# design.net
KiCad netlist of a schematic drawn in Altium Designer
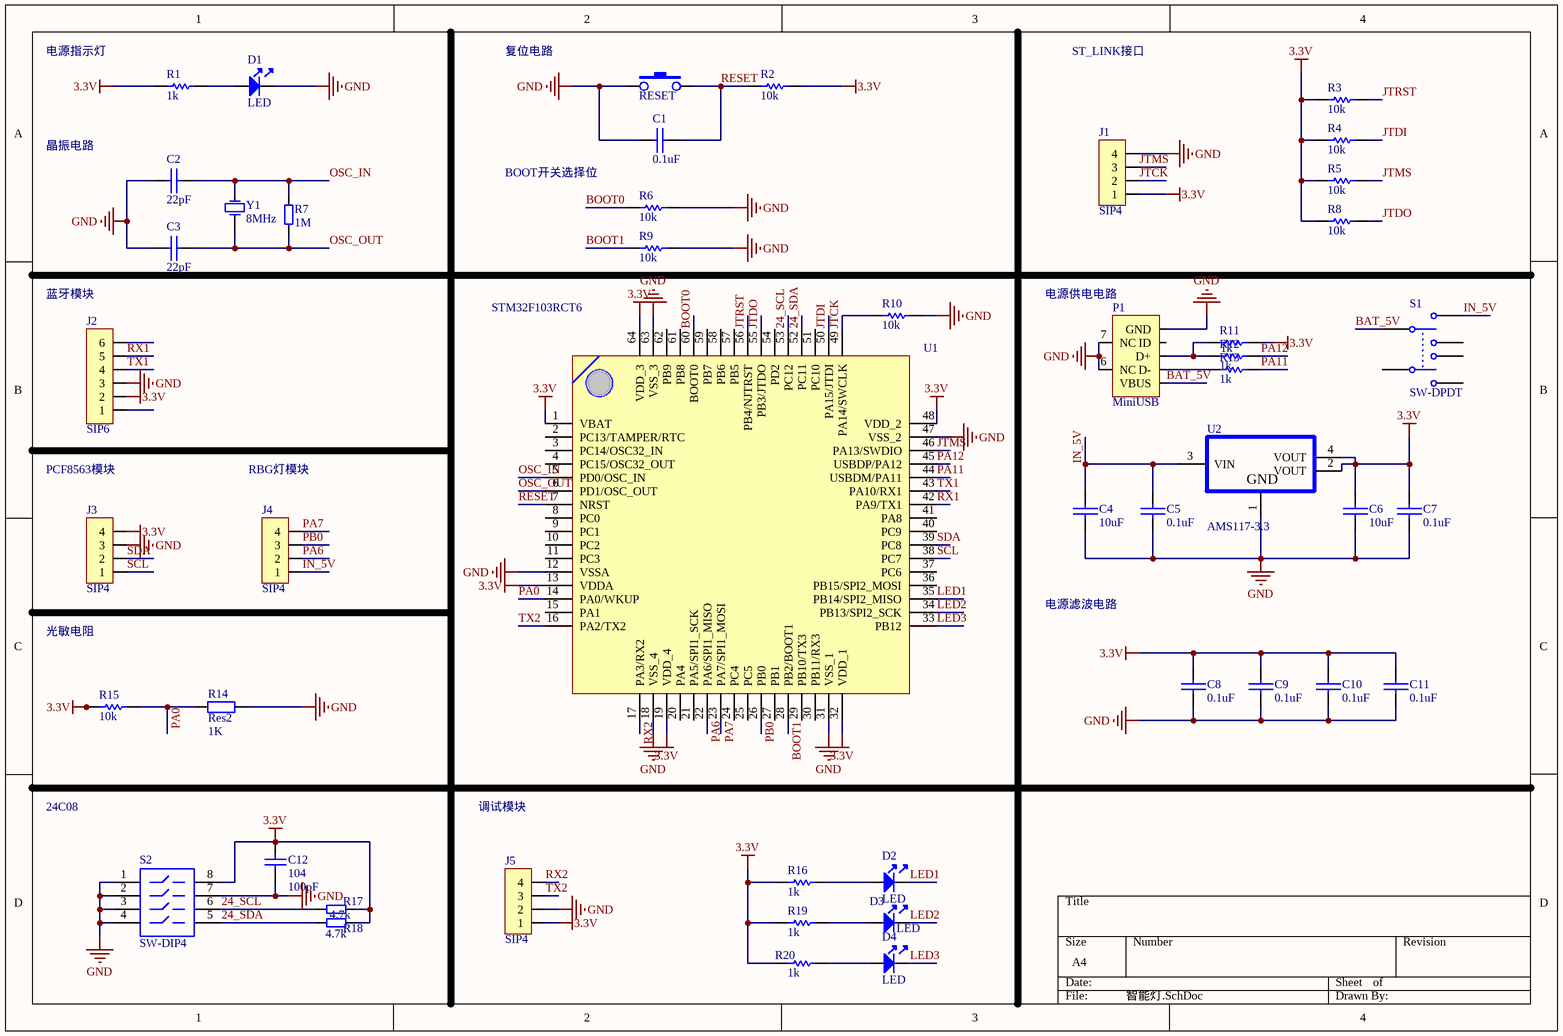
[diagram p0: 智能灯.SchDoc]

(export (version "E")
  (design (tool "Eeschema 10.0.6"))
  (components
    (comp (ref "C1")
      (value "0.1uF")
      (footprint "0805c")
      (description "Capacitor/小容量电容")
      (libsource (lib "狗尾巴草设计室") (part "CAP"))
    )
    (comp (ref "C2")
      (value "22pF")
      (footprint "0805c")
      (description "Capacitor/小容量电容")
      (libsource (lib "狗尾巴草设计室") (part "CAP"))
    )
    (comp (ref "C3")
      (value "22pF")
      (footprint "0805c")
      (description "Capacitor/小容量电容")
      (libsource (lib "狗尾巴草设计室") (part "CAP"))
    )
    (comp (ref "C4")
      (value "10uF")
      (footprint "0805c")
      (description "Capacitor/小容量电容")
      (libsource (lib "狗尾巴草设计室") (part "CAP"))
    )
    (comp (ref "C5")
      (value "0.1uF")
      (footprint "0805c")
      (description "Capacitor/小容量电容")
      (libsource (lib "狗尾巴草设计室") (part "CAP"))
    )
    (comp (ref "C6")
      (value "10uF")
      (footprint "0805c")
      (description "Capacitor/小容量电容")
      (libsource (lib "狗尾巴草设计室") (part "CAP"))
    )
    (comp (ref "C7")
      (value "0.1uF")
      (footprint "0805c")
      (description "Capacitor/小容量电容")
      (libsource (lib "狗尾巴草设计室") (part "CAP"))
    )
    (comp (ref "C8")
      (value "0.1uF")
      (footprint "0805c")
      (description "Capacitor/小容量电容")
      (libsource (lib "狗尾巴草设计室") (part "CAP"))
    )
    (comp (ref "C9")
      (value "0.1uF")
      (footprint "0805c")
      (description "Capacitor/小容量电容")
      (libsource (lib "狗尾巴草设计室") (part "CAP"))
    )
    (comp (ref "C10")
      (value "0.1uF")
      (footprint "0805c")
      (description "Capacitor/小容量电容")
      (libsource (lib "狗尾巴草设计室") (part "CAP"))
    )
    (comp (ref "C11")
      (value "0.1uF")
      (footprint "0805c")
      (description "Capacitor/小容量电容")
      (libsource (lib "狗尾巴草设计室") (part "CAP"))
    )
    (comp (ref "C12")
      (value "104")
      (footprint "0805C")
      (description "Capacitor")
      (fields (field (name "ALTIUM_VALUE") "100pF") (field (name "PUBLISHER") "Altium Limited"))
      (libsource (lib "Miscellaneous Devices") (part "Cap"))
    )
    (comp (ref "D1") (value "LED") (footprint "0805d") (libsource (lib "狗尾巴草设计室") (part "LED")))
    (comp (ref "D2") (value "LED") (footprint "0805d") (libsource (lib "狗尾巴草设计室") (part "LED")))
    (comp (ref "D3") (value "LED") (footprint "0805d") (libsource (lib "狗尾巴草设计室") (part "LED")))
    (comp (ref "D4") (value "LED") (footprint "0805d") (libsource (lib "狗尾巴草设计室") (part "LED")))
    (comp (ref "J1") (value "SIP4") (footprint "P4_2.54-1") (libsource (lib "狗尾巴草设计室") (part "SIP4")))
    (comp (ref "J2") (value "SIP6") (footprint "P6_2.54-3") (libsource (lib "狗尾巴草设计室") (part "SIP6")))
    (comp (ref "J3") (value "SIP4") (footprint "P4_2.54-3") (libsource (lib "狗尾巴草设计室") (part "SIP4")))
    (comp (ref "J4") (value "SIP4") (footprint "P4_2.54-1") (libsource (lib "狗尾巴草设计室") (part "SIP4")))
    (comp (ref "J5") (value "SIP4") (footprint "P4_2.54-1") (libsource (lib "狗尾巴草设计室") (part "SIP4")))
    (comp (ref "P1") (value "MiniUSB") (footprint "USB_MINI_5P") (libsource (lib "狗尾巴草设计室") (part "MiniUSB")))
    (comp (ref "R1") (value "1k") (footprint "0805r") (libsource (lib "狗尾巴草设计室") (part "Res")))
    (comp (ref "R2") (value "10k") (footprint "0805r") (libsource (lib "狗尾巴草设计室") (part "Res")))
    (comp (ref "R3") (value "10k") (footprint "0805r") (libsource (lib "狗尾巴草设计室") (part "Res")))
    (comp (ref "R4") (value "10k") (footprint "0805r") (libsource (lib "狗尾巴草设计室") (part "Res")))
    (comp (ref "R5") (value "10k") (footprint "0805r") (libsource (lib "狗尾巴草设计室") (part "Res")))
    (comp (ref "R6") (value "10k") (footprint "0805r") (libsource (lib "狗尾巴草设计室") (part "Res")))
    (comp (ref "R7") (value "1M") (footprint "0805R") (libsource (lib "狗尾巴草设计室") (part "Res1")))
    (comp (ref "R8") (value "10k") (footprint "0805r") (libsource (lib "狗尾巴草设计室") (part "Res")))
    (comp (ref "R9") (value "10k") (footprint "0805r") (libsource (lib "狗尾巴草设计室") (part "Res")))
    (comp (ref "R10") (value "10k") (footprint "0805r") (libsource (lib "狗尾巴草设计室") (part "Res")))
    (comp (ref "R11") (value "1k") (footprint "0805r") (libsource (lib "狗尾巴草设计室") (part "Res")))
    (comp (ref "R12") (value "1k") (footprint "0805r") (libsource (lib "狗尾巴草设计室") (part "Res")))
    (comp (ref "R13") (value "1k") (footprint "0805r") (libsource (lib "狗尾巴草设计室") (part "Res")))
    (comp (ref "R14")
      (value "Res2")
      (footprint "AXIAL0.3")
      (description "Resistor")
      (fields (field (name "ALTIUM_VALUE") "1K") (field (name "PUBLISHER") "Altium Limited"))
      (libsource (lib "Miscellaneous Devices") (part "Res2"))
    )
    (comp (ref "R15") (value "10k") (footprint "0805R") (libsource (lib "狗尾巴草设计室") (part "Res_1")))
    (comp (ref "R16") (value "1k") (footprint "0603R") (libsource (lib "狗尾巴草设计室") (part "Res_2")))
    (comp (ref "R17") (value "4.7k") (footprint "0805R") (libsource (lib "狗尾巴草设计室") (part "Res1")))
    (comp (ref "R18") (value "4.7k") (footprint "0805R") (libsource (lib "狗尾巴草设计室") (part "Res1")))
    (comp (ref "R19") (value "1k") (footprint "0603R") (libsource (lib "狗尾巴草设计室") (part "Res_2")))
    (comp (ref "R20") (value "1k") (footprint "0603R") (libsource (lib "狗尾巴草设计室") (part "Res_2")))
    (comp (ref "RESET")
      (value "SW-PB_DIP")
      (footprint "KEY_SIM2P")
      (libsource (lib "狗尾巴草设计室") (part "SW-PB_DIP"))
    )
    (comp (ref "S1")
      (value "SW-DPDT")
      (footprint "DPDT-6")
      (description "Double-Pole, Double-Throw Switch")
      (fields (field (name "PUBLISHER") "Altium Limited"))
      (libsource (lib "Miscellaneous Devices") (part "SW-DPDT"))
    )
    (comp (ref "S2")
      (value "SW-DIP4")
      (footprint "DIP-8")
      (description "DIP Switch")
      (fields (field (name "PUBLISHER") "Altium Limited"))
      (libsource (lib "Miscellaneous Devices") (part "SW-DIP4"))
    )
    (comp (ref "U1")
      (value "STM32F103RCT6")
      (footprint "LQFP64-0.5MM")
      (description "LQFP64")
      (libsource (lib "狗尾巴草设计室") (part "STM32F103RD"))
    )
    (comp (ref "U2")
      (value "AMS117-3.3")
      (footprint "SOT-223")
      (libsource (lib "狗尾巴草设计室") (part "AMS117-3.3"))
    )
    (comp (ref "Y1") (value "8MHz") (footprint "0.1UF") (libsource (lib "狗尾巴草设计室") (part "J晶振-3")))
  )
  (nets
    (net (code "1") (name "/24_SCL") (class "Default")
      (node (ref "R17") (pin "1") (pintype "passive"))
      (node (ref "S2") (pin "6") (pinfunction "6_6") (pintype "passive"))
      (node (ref "U1") (pin "53") (pinfunction "PC12_53") (pintype "passive"))
    )
    (net (code "2") (name "/24_SDA") (class "Default")
      (node (ref "R18") (pin "1") (pintype "passive"))
      (node (ref "S2") (pin "5") (pinfunction "5_5") (pintype "passive"))
      (node (ref "U1") (pin "52") (pinfunction "PC11_52") (pintype "passive"))
    )
    (net (code "3") (name "/BAT_5V") (class "Default")
      (node (ref "P1") (pin "1") (pinfunction "VBUS_1") (pintype "passive"))
      (node (ref "S1") (pin "1") (pinfunction "1_1") (pintype "passive"))
    )
    (net (code "4") (name "/BOOT0") (class "Default")
      (node (ref "R6") (pin "1") (pinfunction "1_1") (pintype "passive"))
      (node (ref "U1") (pin "60") (pinfunction "BOOT0_60") (pintype "passive"))
    )
    (net (code "5") (name "/BOOT1") (class "Default")
      (node (ref "R9") (pin "1") (pinfunction "1_1") (pintype "passive"))
      (node (ref "U1") (pin "28") (pinfunction "PB2/BOOT1_28") (pintype "passive"))
    )
    (net (code "6") (name "/IN_5V") (class "Default")
      (node (ref "C4") (pin "1") (pinfunction "1_1") (pintype "passive"))
      (node (ref "C5") (pin "1") (pinfunction "1_1") (pintype "passive"))
      (node (ref "J4") (pin "1") (pinfunction "1_1") (pintype "passive"))
      (node (ref "S1") (pin "2") (pinfunction "2_2") (pintype "passive"))
      (node (ref "U2") (pin "3") (pinfunction "VIN_3") (pintype "passive"))
    )
    (net (code "7") (name "/JTCK") (class "Default")
      (node (ref "J1") (pin "2") (pinfunction "2_2") (pintype "passive"))
      (node (ref "R10") (pin "1") (pinfunction "1_1") (pintype "passive"))
      (node (ref "U1") (pin "49") (pinfunction "PA14/SWCLK_49") (pintype "passive"))
    )
    (net (code "8") (name "/JTDI") (class "Default")
      (node (ref "R4") (pin "2") (pinfunction "2_2") (pintype "passive"))
      (node (ref "U1") (pin "50") (pinfunction "PA15/JTDI_50") (pintype "passive"))
    )
    (net (code "9") (name "/JTDO") (class "Default")
      (node (ref "R8") (pin "2") (pinfunction "2_2") (pintype "passive"))
      (node (ref "U1") (pin "55") (pinfunction "PB3/JTDO_55") (pintype "passive"))
    )
    (net (code "10") (name "/JTMS") (class "Default")
      (node (ref "J1") (pin "3") (pinfunction "3_3") (pintype "passive"))
      (node (ref "R5") (pin "2") (pinfunction "2_2") (pintype "passive"))
      (node (ref "U1") (pin "46") (pinfunction "PA13/SWDIO_46") (pintype "passive"))
    )
    (net (code "11") (name "/JTRST") (class "Default")
      (node (ref "R3") (pin "2") (pinfunction "2_2") (pintype "passive"))
      (node (ref "U1") (pin "56") (pinfunction "PB4/NJTRST_56") (pintype "passive"))
    )
    (net (code "12") (name "/LED1") (class "Default")
      (node (ref "D2") (pin "2") (pinfunction "2_2") (pintype "passive"))
      (node (ref "U1") (pin "35") (pinfunction "PB14/SPI2_MISO_35") (pintype "passive"))
    )
    (net (code "13") (name "/LED2") (class "Default")
      (node (ref "D3") (pin "2") (pinfunction "2_2") (pintype "passive"))
      (node (ref "U1") (pin "34") (pinfunction "PB13/SPI2_SCK_34") (pintype "passive"))
    )
    (net (code "14") (name "/LED3") (class "Default")
      (node (ref "D4") (pin "2") (pinfunction "2_2") (pintype "passive"))
      (node (ref "U1") (pin "33") (pinfunction "PB12_33") (pintype "passive"))
    )
    (net (code "15") (name "/OSC_IN") (class "Default")
      (node (ref "C2") (pin "2") (pinfunction "2_2") (pintype "passive"))
      (node (ref "R7") (pin "1") (pintype "passive"))
      (node (ref "U1") (pin "5") (pinfunction "PD0/OSC_IN_5") (pintype "passive"))
      (node (ref "Y1") (pin "2") (pinfunction "OSC2_2") (pintype "passive"))
    )
    (net (code "16") (name "/OSC_OUT") (class "Default")
      (node (ref "C3") (pin "2") (pinfunction "2_2") (pintype "passive"))
      (node (ref "R7") (pin "2") (pintype "passive"))
      (node (ref "U1") (pin "6") (pinfunction "PD1/OSC_OUT_6") (pintype "passive"))
      (node (ref "Y1") (pin "1") (pinfunction "OSC1_1") (pintype "passive"))
    )
    (net (code "17") (name "/PA0") (class "Default")
      (node (ref "R14") (pin "1") (pinfunction "1_1") (pintype "passive"))
      (node (ref "R15") (pin "2") (pinfunction "2_2") (pintype "passive"))
      (node (ref "U1") (pin "14") (pinfunction "PA0/WKUP_14") (pintype "passive"))
    )
    (net (code "18") (name "/PA6") (class "Default")
      (node (ref "J4") (pin "2") (pinfunction "2_2") (pintype "passive"))
      (node (ref "U1") (pin "22") (pinfunction "PA6/SPI1_MISO_22") (pintype "passive"))
    )
    (net (code "19") (name "/PA7") (class "Default")
      (node (ref "J4") (pin "4") (pinfunction "4_4") (pintype "passive"))
      (node (ref "U1") (pin "23") (pinfunction "PA7/SPI1_MOSI_23") (pintype "passive"))
    )
    (net (code "20") (name "/PA11") (class "Default")
      (node (ref "R13") (pin "2") (pinfunction "2_2") (pintype "passive"))
      (node (ref "U1") (pin "44") (pinfunction "USBDM/PA11_44") (pintype "passive"))
    )
    (net (code "21") (name "/PA12") (class "Default")
      (node (ref "R12") (pin "2") (pinfunction "2_2") (pintype "passive"))
      (node (ref "U1") (pin "45") (pinfunction "USBDP/PA12_45") (pintype "passive"))
    )
    (net (code "22") (name "/PB0") (class "Default")
      (node (ref "J4") (pin "3") (pinfunction "3_3") (pintype "passive"))
      (node (ref "U1") (pin "26") (pinfunction "PB0_26") (pintype "passive"))
    )
    (net (code "23") (name "/RESET") (class "Default")
      (node (ref "C1") (pin "1") (pinfunction "1_1") (pintype "passive"))
      (node (ref "R2") (pin "1") (pinfunction "1_1") (pintype "passive"))
      (node (ref "RESET") (pin "2") (pintype "passive"))
      (node (ref "U1") (pin "7") (pinfunction "NRST_7") (pintype "passive"))
    )
    (net (code "24") (name "/RX1") (class "Default")
      (node (ref "J2") (pin "5") (pinfunction "5_5") (pintype "passive"))
      (node (ref "U1") (pin "42") (pinfunction "PA9/TX1_42") (pintype "passive"))
    )
    (net (code "25") (name "/RX2") (class "Default")
      (node (ref "J5") (pin "4") (pinfunction "4_4") (pintype "passive"))
      (node (ref "U1") (pin "17") (pinfunction "PA3/RX2_17") (pintype "passive"))
    )
    (net (code "26") (name "/SCL") (class "Default")
      (node (ref "J3") (pin "1") (pinfunction "1_1") (pintype "passive"))
      (node (ref "U1") (pin "38") (pinfunction "PC7_38") (pintype "passive"))
    )
    (net (code "27") (name "/SDA") (class "Default")
      (node (ref "J3") (pin "2") (pinfunction "2_2") (pintype "passive"))
      (node (ref "U1") (pin "39") (pinfunction "PC8_39") (pintype "passive"))
    )
    (net (code "28") (name "/TX1") (class "Default")
      (node (ref "J2") (pin "4") (pinfunction "4_4") (pintype "passive"))
      (node (ref "U1") (pin "43") (pinfunction "PA10/RX1_43") (pintype "passive"))
    )
    (net (code "29") (name "/TX2") (class "Default")
      (node (ref "J5") (pin "3") (pinfunction "3_3") (pintype "passive"))
      (node (ref "U1") (pin "16") (pinfunction "PA2/TX2_16") (pintype "passive"))
    )
    (net (code "30") (name "3.3V") (class "Default")
      (node (ref "C10") (pin "1") (pinfunction "1_1") (pintype "passive"))
      (node (ref "C11") (pin "1") (pinfunction "1_1") (pintype "passive"))
      (node (ref "C12") (pin "2") (pinfunction "2_2") (pintype "passive"))
      (node (ref "C6") (pin "1") (pinfunction "1_1") (pintype "passive"))
      (node (ref "C7") (pin "1") (pinfunction "1_1") (pintype "passive"))
      (node (ref "C8") (pin "1") (pinfunction "1_1") (pintype "passive"))
      (node (ref "C9") (pin "1") (pinfunction "1_1") (pintype "passive"))
      (node (ref "J1") (pin "1") (pinfunction "1_1") (pintype "passive"))
      (node (ref "J2") (pin "2") (pinfunction "2_2") (pintype "passive"))
      (node (ref "J3") (pin "4") (pinfunction "4_4") (pintype "passive"))
      (node (ref "J5") (pin "1") (pinfunction "1_1") (pintype "passive"))
      (node (ref "R1") (pin "1") (pinfunction "1_1") (pintype "passive"))
      (node (ref "R11") (pin "2") (pinfunction "2_2") (pintype "passive"))
      (node (ref "R15") (pin "1") (pinfunction "1_1") (pintype "passive"))
      (node (ref "R16") (pin "1") (pinfunction "1_1") (pintype "passive"))
      (node (ref "R17") (pin "2") (pintype "passive"))
      (node (ref "R18") (pin "2") (pintype "passive"))
      (node (ref "R19") (pin "1") (pinfunction "1_1") (pintype "passive"))
      (node (ref "R2") (pin "2") (pinfunction "2_2") (pintype "passive"))
      (node (ref "R20") (pin "1") (pinfunction "1_1") (pintype "passive"))
      (node (ref "R3") (pin "1") (pinfunction "1_1") (pintype "passive"))
      (node (ref "R4") (pin "1") (pinfunction "1_1") (pintype "passive"))
      (node (ref "R5") (pin "1") (pinfunction "1_1") (pintype "passive"))
      (node (ref "R8") (pin "1") (pinfunction "1_1") (pintype "passive"))
      (node (ref "S2") (pin "8") (pinfunction "8_8") (pintype "passive"))
      (node (ref "U1") (pin "1") (pinfunction "VBAT_1") (pintype "passive"))
      (node (ref "U1") (pin "13") (pinfunction "VDDA_13") (pintype "passive"))
      (node (ref "U1") (pin "19") (pinfunction "VDD_4_19") (pintype "passive"))
      (node (ref "U1") (pin "32") (pinfunction "VDD_1_32") (pintype "passive"))
      (node (ref "U1") (pin "48") (pinfunction "VDD_2_48") (pintype "passive"))
      (node (ref "U1") (pin "64") (pinfunction "VDD_3_64") (pintype "passive"))
      (node (ref "U2") (pin "2") (pinfunction "VOUT_2") (pintype "passive"))
      (node (ref "U2") (pin "4") (pinfunction "VOUT_4") (pintype "passive"))
    )
    (net (code "31") (name "GND") (class "Default")
      (node (ref "C1") (pin "2") (pinfunction "2_2") (pintype "passive"))
      (node (ref "C10") (pin "2") (pinfunction "2_2") (pintype "passive"))
      (node (ref "C11") (pin "2") (pinfunction "2_2") (pintype "passive"))
      (node (ref "C12") (pin "1") (pinfunction "1_1") (pintype "passive"))
      (node (ref "C2") (pin "1") (pinfunction "1_1") (pintype "passive"))
      (node (ref "C3") (pin "1") (pinfunction "1_1") (pintype "passive"))
      (node (ref "C4") (pin "2") (pinfunction "2_2") (pintype "passive"))
      (node (ref "C5") (pin "2") (pinfunction "2_2") (pintype "passive"))
      (node (ref "C6") (pin "2") (pinfunction "2_2") (pintype "passive"))
      (node (ref "C7") (pin "2") (pinfunction "2_2") (pintype "passive"))
      (node (ref "C8") (pin "2") (pinfunction "2_2") (pintype "passive"))
      (node (ref "C9") (pin "2") (pinfunction "2_2") (pintype "passive"))
      (node (ref "D1") (pin "2") (pinfunction "2_2") (pintype "passive"))
      (node (ref "J1") (pin "4") (pinfunction "4_4") (pintype "passive"))
      (node (ref "J2") (pin "3") (pinfunction "3_3") (pintype "passive"))
      (node (ref "J3") (pin "3") (pinfunction "3_3") (pintype "passive"))
      (node (ref "J5") (pin "2") (pinfunction "2_2") (pintype "passive"))
      (node (ref "P1") (pin "5") (pinfunction "GND_5") (pintype "passive"))
      (node (ref "P1") (pin "6") (pinfunction "NC_6") (pintype "passive"))
      (node (ref "P1") (pin "7") (pinfunction "NC_7") (pintype "passive"))
      (node (ref "R10") (pin "2") (pinfunction "2_2") (pintype "passive"))
      (node (ref "R14") (pin "2") (pinfunction "2_2") (pintype "passive"))
      (node (ref "R6") (pin "2") (pinfunction "2_2") (pintype "passive"))
      (node (ref "R9") (pin "2") (pinfunction "2_2") (pintype "passive"))
      (node (ref "RESET") (pin "1") (pintype "passive"))
      (node (ref "S2") (pin "1") (pinfunction "1_1") (pintype "passive"))
      (node (ref "S2") (pin "2") (pinfunction "2_2") (pintype "passive"))
      (node (ref "S2") (pin "3") (pinfunction "3_3") (pintype "passive"))
      (node (ref "S2") (pin "4") (pinfunction "4_4") (pintype "passive"))
      (node (ref "S2") (pin "7") (pinfunction "7_7") (pintype "passive"))
      (node (ref "U1") (pin "12") (pinfunction "VSSA_12") (pintype "passive"))
      (node (ref "U1") (pin "18") (pinfunction "VSS_4_18") (pintype "passive"))
      (node (ref "U1") (pin "31") (pinfunction "VSS_1_31") (pintype "passive"))
      (node (ref "U1") (pin "47") (pinfunction "VSS_2_47") (pintype "passive"))
      (node (ref "U1") (pin "63") (pinfunction "VSS_3_63") (pintype "passive"))
      (node (ref "U2") (pin "1") (pinfunction "GND_1") (pintype "passive"))
    )
    (net (code "32") (name "Net-(D1-Pad1)") (class "Default")
      (node (ref "D1") (pin "1") (pinfunction "1_1") (pintype "passive"))
      (node (ref "R1") (pin "2") (pinfunction "2_2") (pintype "passive"))
    )
    (net (code "33") (name "Net-(D2-Pad1)") (class "Default")
      (node (ref "D2") (pin "1") (pinfunction "1_1") (pintype "passive"))
      (node (ref "R16") (pin "2") (pinfunction "2_2") (pintype "passive"))
    )
    (net (code "34") (name "Net-(D3-Pad1)") (class "Default")
      (node (ref "D3") (pin "1") (pinfunction "1_1") (pintype "passive"))
      (node (ref "R19") (pin "2") (pinfunction "2_2") (pintype "passive"))
    )
    (net (code "35") (name "Net-(D4-Pad1)") (class "Default")
      (node (ref "D4") (pin "1") (pinfunction "1_1") (pintype "passive"))
      (node (ref "R20") (pin "2") (pinfunction "2_2") (pintype "passive"))
    )
    (net (code "36") (name "Net-(P1-D+)") (class "Default")
      (node (ref "P1") (pin "3") (pinfunction "D+_3") (pintype "passive"))
      (node (ref "R11") (pin "1") (pinfunction "1_1") (pintype "passive"))
      (node (ref "R12") (pin "1") (pinfunction "1_1") (pintype "passive"))
    )
    (net (code "37") (name "Net-(P1-D-)") (class "Default")
      (node (ref "P1") (pin "2") (pinfunction "D-_2") (pintype "passive"))
      (node (ref "R13") (pin "1") (pinfunction "1_1") (pintype "passive"))
    )
    (net (code "38") (name "unconnected-(J2-Pad1)") (class "Default")
      (node (ref "J2") (pin "1") (pinfunction "1_1") (pintype "passive"))
    )
    (net (code "39") (name "unconnected-(J2-Pad6)") (class "Default")
      (node (ref "J2") (pin "6") (pinfunction "6_6") (pintype "passive"))
    )
    (net (code "40") (name "unconnected-(P1-ID-Pad4)") (class "Default")
      (node (ref "P1") (pin "4") (pinfunction "ID_4") (pintype "passive"))
    )
    (net (code "41") (name "unconnected-(S1-Pad3)") (class "Default")
      (node (ref "S1") (pin "3") (pinfunction "3_3") (pintype "passive"))
    )
    (net (code "42") (name "unconnected-(S1-Pad4)") (class "Default")
      (node (ref "S1") (pin "4") (pinfunction "4_4") (pintype "passive"))
    )
    (net (code "43") (name "unconnected-(S1-Pad5)") (class "Default")
      (node (ref "S1") (pin "5") (pinfunction "5_5") (pintype "passive"))
    )
    (net (code "44") (name "unconnected-(S1-Pad6)") (class "Default")
      (node (ref "S1") (pin "6") (pinfunction "6_6") (pintype "passive"))
    )
    (net (code "45") (name "unconnected-(U1-PA1-Pad15)") (class "Default")
      (node (ref "U1") (pin "15") (pinfunction "PA1_15") (pintype "passive"))
    )
    (net (code "46") (name "unconnected-(U1-PA4-Pad20)") (class "Default")
      (node (ref "U1") (pin "20") (pinfunction "PA4_20") (pintype "passive"))
    )
    (net (code "47") (name "unconnected-(U1-PA5{slash}SPI1_SCK-Pad21)") (class "Default")
      (node (ref "U1") (pin "21") (pinfunction "PA5/SPI1_SCK_21") (pintype "passive"))
    )
    (net (code "48") (name "unconnected-(U1-PA8-Pad41)") (class "Default")
      (node (ref "U1") (pin "41") (pinfunction "PA8_41") (pintype "passive"))
    )
    (net (code "49") (name "unconnected-(U1-PB1-Pad27)") (class "Default")
      (node (ref "U1") (pin "27") (pinfunction "PB1_27") (pintype "passive"))
    )
    (net (code "50") (name "unconnected-(U1-PB5-Pad57)") (class "Default")
      (node (ref "U1") (pin "57") (pinfunction "PB5_57") (pintype "passive"))
    )
    (net (code "51") (name "unconnected-(U1-PB6-Pad58)") (class "Default")
      (node (ref "U1") (pin "58") (pinfunction "PB6_58") (pintype "passive"))
    )
    (net (code "52") (name "unconnected-(U1-PB7-Pad59)") (class "Default")
      (node (ref "U1") (pin "59") (pinfunction "PB7_59") (pintype "passive"))
    )
    (net (code "53") (name "unconnected-(U1-PB8-Pad61)") (class "Default")
      (node (ref "U1") (pin "61") (pinfunction "PB8_61") (pintype "passive"))
    )
    (net (code "54") (name "unconnected-(U1-PB9-Pad62)") (class "Default")
      (node (ref "U1") (pin "62") (pinfunction "PB9_62") (pintype "passive"))
    )
    (net (code "55") (name "unconnected-(U1-PB10{slash}TX3-Pad29)") (class "Default")
      (node (ref "U1") (pin "29") (pinfunction "PB10/TX3_29") (pintype "passive"))
    )
    (net (code "56") (name "unconnected-(U1-PB11{slash}RX3-Pad30)") (class "Default")
      (node (ref "U1") (pin "30") (pinfunction "PB11/RX3_30") (pintype "passive"))
    )
    (net (code "57") (name "unconnected-(U1-PB15{slash}SPI2_MOSI-Pad36)") (class "Default")
      (node (ref "U1") (pin "36") (pinfunction "PB15/SPI2_MOSI_36") (pintype "passive"))
    )
    (net (code "58") (name "unconnected-(U1-PC0-Pad8)") (class "Default")
      (node (ref "U1") (pin "8") (pinfunction "PC0_8") (pintype "passive"))
    )
    (net (code "59") (name "unconnected-(U1-PC1-Pad9)") (class "Default")
      (node (ref "U1") (pin "9") (pinfunction "PC1_9") (pintype "passive"))
    )
    (net (code "60") (name "unconnected-(U1-PC2-Pad10)") (class "Default")
      (node (ref "U1") (pin "10") (pinfunction "PC2_10") (pintype "passive"))
    )
    (net (code "61") (name "unconnected-(U1-PC3-Pad11)") (class "Default")
      (node (ref "U1") (pin "11") (pinfunction "PC3_11") (pintype "passive"))
    )
    (net (code "62") (name "unconnected-(U1-PC4-Pad24)") (class "Default")
      (node (ref "U1") (pin "24") (pinfunction "PC4_24") (pintype "passive"))
    )
    (net (code "63") (name "unconnected-(U1-PC5-Pad25)") (class "Default")
      (node (ref "U1") (pin "25") (pinfunction "PC5_25") (pintype "passive"))
    )
    (net (code "64") (name "unconnected-(U1-PC6-Pad37)") (class "Default")
      (node (ref "U1") (pin "37") (pinfunction "PC6_37") (pintype "passive"))
    )
    (net (code "65") (name "unconnected-(U1-PC9-Pad40)") (class "Default")
      (node (ref "U1") (pin "40") (pinfunction "PC9_40") (pintype "passive"))
    )
    (net (code "66") (name "unconnected-(U1-PC10-Pad51)") (class "Default")
      (node (ref "U1") (pin "51") (pinfunction "PC10_51") (pintype "passive"))
    )
    (net (code "67") (name "unconnected-(U1-PC13{slash}TAMPER{slash}RTC-Pad2)") (class "Default")
      (node (ref "U1") (pin "2") (pinfunction "PC13/TAMPER/RTC_2") (pintype "passive"))
    )
    (net (code "68") (name "unconnected-(U1-PC14{slash}OSC32_IN-Pad3)") (class "Default")
      (node (ref "U1") (pin "3") (pinfunction "PC14/OSC32_IN_3") (pintype "passive"))
    )
    (net (code "69") (name "unconnected-(U1-PC15{slash}OSC32_OUT-Pad4)") (class "Default")
      (node (ref "U1") (pin "4") (pinfunction "PC15/OSC32_OUT_4") (pintype "passive"))
    )
    (net (code "70") (name "unconnected-(U1-PD2-Pad54)") (class "Default")
      (node (ref "U1") (pin "54") (pinfunction "PD2_54") (pintype "passive"))
    )
  )
)
